# PWR.net
KiCad netlist of a schematic drawn in Altium Designer
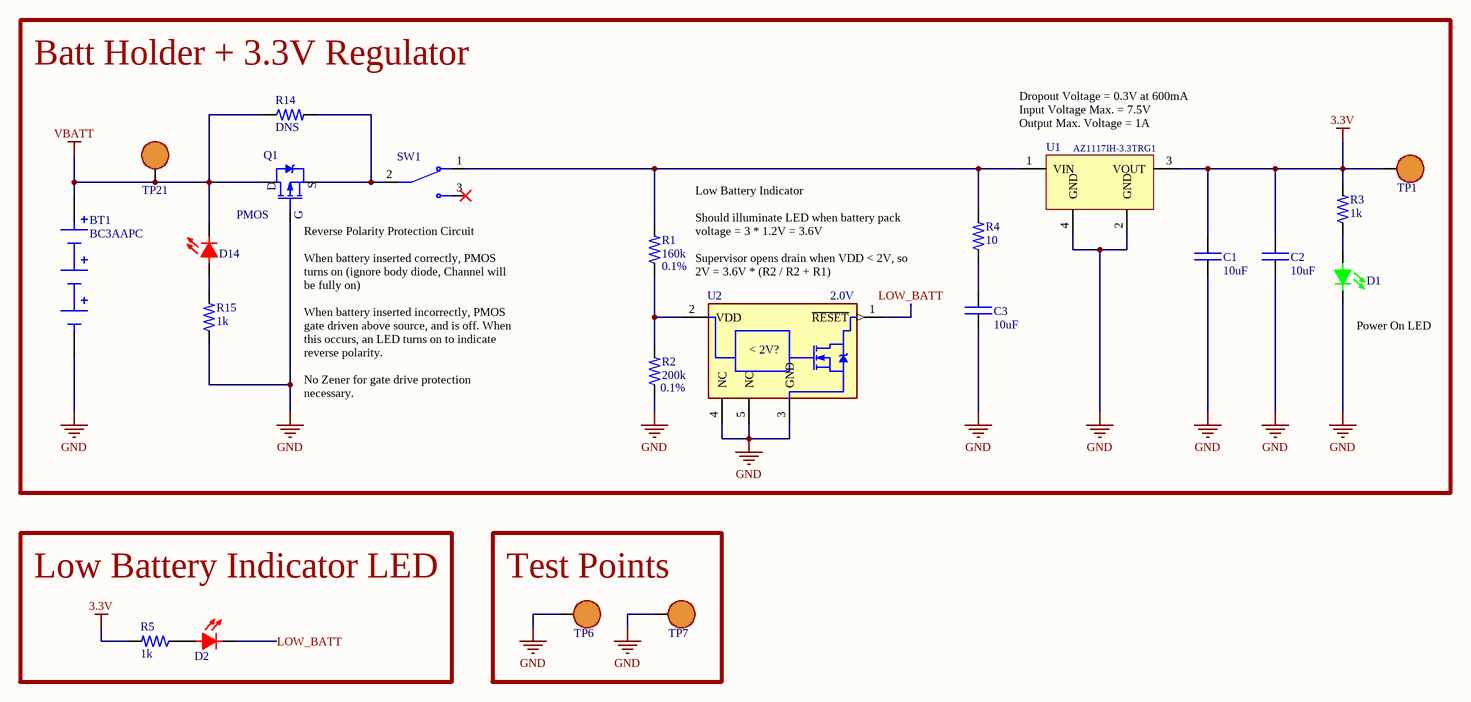
[diagram p0: PWR.SchDoc]

(export (version "E")
  (design (tool "Eeschema 10.0.6"))
  (components
    (comp (ref "BT1")
      (value "BC3AAPC")
      (footprint "Christmas-2024_TSO-PCB:BAT_BC3AAPC")
      (description "Holder Batt 3-AA Cells Pc Mnt")
      (fields (field (name "MFR") "MPD (Memory Protection Devices)"))
      (libsource (lib "Christmas-2024_TSO-PCB") (part "BC3AAPC"))
    )
    (comp (ref "C1")
      (value "10uF")
      (footprint "Christmas-2024_TSO-PCB:0603C")
      (description "Capacitor")
      (fields (field (name "MFR") "Samsung") (field (name "Comment") "CAP"))
      (libsource (lib "Christmas-2024_TSO-PCB") (part "CAP"))
    )
    (comp (ref "C2")
      (value "10uF")
      (footprint "Christmas-2024_TSO-PCB:0603C")
      (description "Capacitor")
      (fields (field (name "MFR") "Samsung") (field (name "Comment") "CAP"))
      (libsource (lib "Christmas-2024_TSO-PCB") (part "CAP"))
    )
    (comp (ref "C3")
      (value "10uF")
      (footprint "Christmas-2024_TSO-PCB:0603C")
      (description "Capacitor")
      (fields (field (name "MFR") "Samsung") (field (name "Comment") "CAP"))
      (libsource (lib "Christmas-2024_TSO-PCB") (part "CAP"))
    )
    (comp (ref "D1")
      (value "LED - GREEN")
      (footprint "Christmas-2024_TSO-PCB:LED - 0603 - GREEN")
      (description "LED, Green, 0603")
      (fields (field (name "MFR") "Dialight"))
      (libsource (lib "Christmas-2024_TSO-PCB") (part "LED - GREEN"))
    )
    (comp (ref "D2")
      (value "LED - RED")
      (footprint "Christmas-2024_TSO-PCB:LED - 0603 - RED")
      (description "LED, Red, 0603")
      (fields (field (name "MFR") "Würth Elektronik"))
      (libsource (lib "Christmas-2024_TSO-PCB") (part "LED - RED"))
    )
    (comp (ref "D14")
      (value "LED - RED")
      (footprint "Christmas-2024_TSO-PCB:LED - 0603 - RED")
      (description "LED, Red, 0603")
      (fields (field (name "MFR") "Würth Elektronik"))
      (libsource (lib "Christmas-2024_TSO-PCB") (part "LED - RED"))
    )
    (comp (ref "Q1")
      (value "PMOS")
      (footprint "Christmas-2024_TSO-PCB:SOT-23")
      (description "P-Channel MOSFET, 4.2A, 20V, , 52mOhm max, 1.4W")
      (fields (field (name "MFR") "Diodes Incorporated"))
      (libsource (lib "Christmas-2024_TSO-PCB") (part "PMOS"))
    )
    (comp (ref "R1")
      (value "160k")
      (footprint "Christmas-2024_TSO-PCB:0402R")
      (description "Resistor")
      (fields (field (name "MFR") "YAGEO") (field (name "TOLERANCE") "0.1%") (field (name "Comment") "RES"))
      (libsource (lib "Christmas-2024_TSO-PCB") (part "RES"))
    )
    (comp (ref "R2")
      (value "200k")
      (footprint "Christmas-2024_TSO-PCB:0402R")
      (description "Resistor")
      (fields (field (name "MFR") "YAGEO") (field (name "TOLERANCE") "0.1%") (field (name "Comment") "RES"))
      (libsource (lib "Christmas-2024_TSO-PCB") (part "RES"))
    )
    (comp (ref "R3")
      (value "1k")
      (footprint "Christmas-2024_TSO-PCB:0402R")
      (description "Resistor")
      (fields (field (name "MFR") "YAGEO") (field (name "Comment") "RES"))
      (libsource (lib "Christmas-2024_TSO-PCB") (part "RES"))
    )
    (comp (ref "R4")
      (value "10")
      (footprint "Christmas-2024_TSO-PCB:0805R")
      (description "Resistor")
      (fields (field (name "MFR") "Vishay Dale") (field (name "Comment") "RES"))
      (libsource (lib "Christmas-2024_TSO-PCB") (part "RES"))
    )
    (comp (ref "R5")
      (value "1k")
      (footprint "Christmas-2024_TSO-PCB:0402R")
      (description "Resistor")
      (fields (field (name "MFR") "YAGEO") (field (name "Comment") "RES"))
      (libsource (lib "Christmas-2024_TSO-PCB") (part "RES"))
    )
    (comp (ref "R14")
      (value "DNS")
      (footprint "Christmas-2024_TSO-PCB:0805R")
      (description "Resistor")
      (fields (field (name "Comment") "RES"))
      (libsource (lib "Christmas-2024_TSO-PCB") (part "RES"))
    )
    (comp (ref "R15")
      (value "1k")
      (footprint "Christmas-2024_TSO-PCB:0402R")
      (description "Resistor")
      (fields (field (name "MFR") "YAGEO") (field (name "Comment") "RES"))
      (libsource (lib "Christmas-2024_TSO-PCB") (part "RES"))
    )
    (comp (ref "SW1")
      (value "SPDT TOGGLE SWITCH")
      (footprint "Christmas-2024_TSO-PCB:SW_100SP1T2B4M6QE")
      (description "Toggle Switch, 100 Series, SPDT, ON-NONE-ON, Sealed, 5A, 120VAC, 28VDC, R/A PC")
      (fields (field (name "MFR") "E-Switch"))
      (libsource (lib "Christmas-2024_TSO-PCB") (part "SPDT TOGGLE SWITCH"))
    )
    (comp (ref "TP1")
      (value "RCWCTE")
      (footprint "Christmas-2024_TSO-PCB:RCWCTE")
      (description "Test Point, Surface Mount")
      (fields (field (name "MFR") "KOA Speer Electronics, Inc."))
      (libsource (lib "Christmas-2024_TSO-PCB") (part "TEST POINT"))
    )
    (comp (ref "TP6")
      (value "RCWCTE")
      (footprint "Christmas-2024_TSO-PCB:RCWCTE")
      (description "Test Point, Surface Mount")
      (fields (field (name "MFR") "KOA Speer Electronics, Inc."))
      (libsource (lib "Christmas-2024_TSO-PCB") (part "TEST POINT"))
    )
    (comp (ref "TP7")
      (value "RCWCTE")
      (footprint "Christmas-2024_TSO-PCB:RCWCTE")
      (description "Test Point, Surface Mount")
      (fields (field (name "MFR") "KOA Speer Electronics, Inc."))
      (libsource (lib "Christmas-2024_TSO-PCB") (part "TEST POINT"))
    )
    (comp (ref "TP21")
      (value "RCWCTE")
      (footprint "Christmas-2024_TSO-PCB:RCWCTE")
      (description "Test Point, Surface Mount")
      (fields (field (name "MFR") "KOA Speer Electronics, Inc."))
      (libsource (lib "Christmas-2024_TSO-PCB") (part "TEST POINT"))
    )
    (comp (ref "U1")
      (value "AZ1117IH-3.3TRG1")
      (footprint "Christmas-2024_TSO-PCB:SOT-223-3")
      (description "IC REG LINEAR 3.3V 1A SOT223")
      (fields (field (name "MFR") "Texas Instruments"))
      (libsource (lib "Christmas-2024_TSO-PCB") (part "LIN REG 3.3V 1A"))
    )
    (comp (ref "U2")
      (value "2.0V")
      (footprint "Christmas-2024_TSO-PCB:SOT-23-5")
      (description "Low-voltage supervisor with adjustable-reset time delay and manual reset")
      (fields (field (name "MFR") "Texas Instruments"))
      (libsource (lib "Christmas-2024_TSO-PCB") (part "SUPERVISOR 2V AL OD"))
    )
  )
  (nets
    (net (code "1") (name "/LOW_BATT") (class "Default")
      (node (ref "D2") (pin "2") (pinfunction "C_2") (pintype "passive"))
      (node (ref "U2") (pin "1") (pinfunction "~{RESET}_1") (pintype "output"))
    )
    (net (code "2") (name "3.3V") (class "Default")
      (node (ref "C1") (pin "2") (pinfunction "2_2") (pintype "passive"))
      (node (ref "C2") (pin "2") (pinfunction "2_2") (pintype "passive"))
      (node (ref "R3") (pin "2") (pinfunction "2_2") (pintype "passive"))
      (node (ref "R5") (pin "2") (pinfunction "2_2") (pintype "passive"))
      (node (ref "TP1") (pin "1") (pinfunction "0_1") (pintype "passive"))
      (node (ref "U1") (pin "3") (pinfunction "VOUT_3") (pintype "passive"))
    )
    (net (code "3") (name "GND") (class "Default")
      (node (ref "BT1") (pin "NEG") (pinfunction "NEG_NEG") (pintype "passive"))
      (node (ref "C1") (pin "1") (pinfunction "1_1") (pintype "passive"))
      (node (ref "C2") (pin "1") (pinfunction "1_1") (pintype "passive"))
      (node (ref "C3") (pin "1") (pinfunction "1_1") (pintype "passive"))
      (node (ref "D1") (pin "2") (pinfunction "C_2") (pintype "passive"))
      (node (ref "Q1") (pin "1") (pinfunction "G_1") (pintype "passive"))
      (node (ref "R15") (pin "1") (pinfunction "1_1") (pintype "passive"))
      (node (ref "R2") (pin "1") (pinfunction "1_1") (pintype "passive"))
      (node (ref "TP6") (pin "1") (pinfunction "0_1") (pintype "passive"))
      (node (ref "TP7") (pin "1") (pinfunction "0_1") (pintype "passive"))
      (node (ref "U1") (pin "2") (pinfunction "GND_2") (pintype "passive"))
      (node (ref "U1") (pin "4") (pinfunction "GND_4") (pintype "passive"))
      (node (ref "U2") (pin "3") (pinfunction "GND_3") (pintype "power_in"))
      (node (ref "U2") (pin "4") (pinfunction "NC_4") (pintype "passive"))
      (node (ref "U2") (pin "5") (pinfunction "NC_5") (pintype "passive"))
    )
    (net (code "4") (name "Net-(C3-Pad2)") (class "Default")
      (node (ref "C3") (pin "2") (pinfunction "2_2") (pintype "passive"))
      (node (ref "R4") (pin "1") (pinfunction "1_1") (pintype "passive"))
    )
    (net (code "5") (name "Net-(D1-A)") (class "Default")
      (node (ref "D1") (pin "1") (pinfunction "A_1") (pintype "passive"))
      (node (ref "R3") (pin "1") (pinfunction "1_1") (pintype "passive"))
    )
    (net (code "6") (name "Net-(D2-A)") (class "Default")
      (node (ref "D2") (pin "1") (pinfunction "A_1") (pintype "passive"))
      (node (ref "R5") (pin "1") (pinfunction "1_1") (pintype "passive"))
    )
    (net (code "7") (name "Net-(D14-A)") (class "Default")
      (node (ref "D14") (pin "1") (pinfunction "A_1") (pintype "passive"))
      (node (ref "R15") (pin "2") (pinfunction "2_2") (pintype "passive"))
    )
    (net (code "8") (name "Net-(Q1-S)") (class "Default")
      (node (ref "Q1") (pin "2") (pinfunction "S_2") (pintype "passive"))
      (node (ref "R14") (pin "2") (pinfunction "2_2") (pintype "passive"))
      (node (ref "SW1") (pin "2") (pinfunction "2_2") (pintype "passive"))
    )
    (net (code "9") (name "Net-(U1-VIN)") (class "Default")
      (node (ref "R1") (pin "2") (pinfunction "2_2") (pintype "passive"))
      (node (ref "R4") (pin "2") (pinfunction "2_2") (pintype "passive"))
      (node (ref "SW1") (pin "1") (pinfunction "1_1") (pintype "passive"))
      (node (ref "U1") (pin "1") (pinfunction "VIN_1") (pintype "passive"))
    )
    (net (code "10") (name "Net-(U2-VDD)") (class "Default")
      (node (ref "R1") (pin "1") (pinfunction "1_1") (pintype "passive"))
      (node (ref "R2") (pin "2") (pinfunction "2_2") (pintype "passive"))
      (node (ref "U2") (pin "2") (pinfunction "VDD_2") (pintype "power_in"))
    )
    (net (code "11") (name "VBATT") (class "Default")
      (node (ref "BT1") (pin "POS") (pinfunction "POS_POS") (pintype "passive"))
      (node (ref "D14") (pin "2") (pinfunction "C_2") (pintype "passive"))
      (node (ref "Q1") (pin "3") (pinfunction "D_3") (pintype "passive"))
      (node (ref "R14") (pin "1") (pinfunction "1_1") (pintype "passive"))
      (node (ref "TP21") (pin "1") (pinfunction "0_1") (pintype "passive"))
    )
    (net (code "12") (name "unconnected-(SW1-Pad3)") (class "Default")
      (node (ref "SW1") (pin "3") (pinfunction "3_3") (pintype "passive+no_connect"))
    )
  )
)
